# CAP_TCH_4xBUT_CY8CMBR2044.net
KiCad netlist of a schematic drawn in Altium Designer
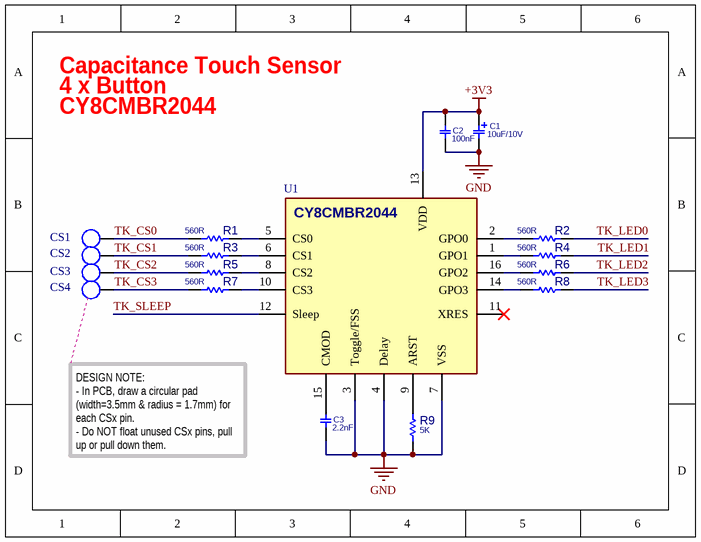
[diagram p0: CAP TCH 4xBUT CY8CMBR2044.SchDoc]

(export (version "E")
  (design (tool "Eeschema 10.0.6"))
  (components
    (comp (ref "C1")
      (value "10uF/10V")
      (footprint "C_TN_3216")
      (description "CAP, SMD, TAN")
      (libsource (lib "Passive") (part "CAP_SMD_TAN"))
    )
    (comp (ref "C2")
      (value "100nF")
      (footprint "C0603")
      (description "CAP, SMD, MLCC")
      (fields (field (name "MANF_P#") "MANF_PART#") (field (name "MANF") "Murata"))
      (libsource (lib "Passive") (part "CAP_SMD_MLCC"))
    )
    (comp (ref "C3")
      (value "2.2nF")
      (footprint "C0603")
      (description "CAP, SMD, MLCC")
      (fields (field (name "MANF_P#") "MANF_PART#") (field (name "MANF") "Murata"))
      (libsource (lib "Passive") (part "CAP_SMD_MLCC"))
    )
    (comp (ref "CS1")
      (value "CAP Sense")
      (footprint "CAP Sense 7mm")
      (libsource (lib "Button") (part "CAP Sense"))
    )
    (comp (ref "CS2")
      (value "CAP Sense")
      (footprint "CAP Sense 7mm")
      (libsource (lib "Button") (part "CAP Sense"))
    )
    (comp (ref "CS3")
      (value "CAP Sense")
      (footprint "CAP Sense 7mm")
      (libsource (lib "Button") (part "CAP Sense"))
    )
    (comp (ref "CS4")
      (value "CAP Sense")
      (footprint "CAP Sense 7mm")
      (libsource (lib "Button") (part "CAP Sense"))
    )
    (comp (ref "R1")
      (value "560R")
      (footprint "R0603")
      (description "RES, SMD")
      (fields (field (name "MANF_P#") "RK73H1ETTP4701F") (field (name "MANF") "KOA SPEER"))
      (libsource (lib "Passive") (part "RES_SMD"))
    )
    (comp (ref "R2")
      (value "560R")
      (footprint "R0603")
      (description "RES, SMD")
      (fields (field (name "MANF_P#") "RK73H1ETTP4701F") (field (name "MANF") "KOA SPEER"))
      (libsource (lib "Passive") (part "RES_SMD"))
    )
    (comp (ref "R3")
      (value "560R")
      (footprint "R0603")
      (description "RES, SMD")
      (fields (field (name "MANF_P#") "RK73H1ETTP4701F") (field (name "MANF") "KOA SPEER"))
      (libsource (lib "Passive") (part "RES_SMD"))
    )
    (comp (ref "R4")
      (value "560R")
      (footprint "R0603")
      (description "RES, SMD")
      (fields (field (name "MANF_P#") "RK73H1ETTP4701F") (field (name "MANF") "KOA SPEER"))
      (libsource (lib "Passive") (part "RES_SMD"))
    )
    (comp (ref "R5")
      (value "560R")
      (footprint "R0603")
      (description "RES, SMD")
      (fields (field (name "MANF_P#") "RK73H1ETTP4701F") (field (name "MANF") "KOA SPEER"))
      (libsource (lib "Passive") (part "RES_SMD"))
    )
    (comp (ref "R6")
      (value "560R")
      (footprint "R0603")
      (description "RES, SMD")
      (fields (field (name "MANF_P#") "RK73H1ETTP4701F") (field (name "MANF") "KOA SPEER"))
      (libsource (lib "Passive") (part "RES_SMD"))
    )
    (comp (ref "R7")
      (value "560R")
      (footprint "R0603")
      (description "RES, SMD")
      (fields (field (name "MANF_P#") "RK73H1ETTP4701F") (field (name "MANF") "KOA SPEER"))
      (libsource (lib "Passive") (part "RES_SMD"))
    )
    (comp (ref "R8")
      (value "560R")
      (footprint "R0603")
      (description "RES, SMD")
      (fields (field (name "MANF_P#") "RK73H1ETTP4701F") (field (name "MANF") "KOA SPEER"))
      (libsource (lib "Passive") (part "RES_SMD"))
    )
    (comp (ref "R9")
      (value "5K")
      (footprint "R0603")
      (description "RES, SMD")
      (fields (field (name "MANF_P#") "RK73H1ETTP4701F") (field (name "MANF") "KOA SPEER"))
      (libsource (lib "Passive") (part "RES_SMD"))
    )
    (comp (ref "U1")
      (value "CY8CMBR2044")
      (footprint "QFN50_16T_3X3")
      (description "CapTouchSensor, 4-CH, QFN16")
      (fields (field (name "MANF") "Microchip") (field (name "MANF_P#") "CAP1208-1-A4"))
      (libsource (lib "Capacitance Touch Sensor") (part "CY8CMBR2044_QFN16"))
    )
  )
  (nets
    (net (code "1") (name "+3V3") (class "Default")
      (node (ref "C1") (pin "1") (pinfunction "1_1") (pintype "passive"))
      (node (ref "C2") (pin "2") (pinfunction "2_2") (pintype "passive"))
      (node (ref "U1") (pin "13") (pinfunction "VDD_13") (pintype "passive"))
    )
    (net (code "2") (name "/TK_CS0") (class "Default")
      (node (ref "CS1") (pin "1") (pinfunction "1_1") (pintype "passive"))
      (node (ref "R1") (pin "1") (pinfunction "1_1") (pintype "passive"))
    )
    (net (code "3") (name "/TK_CS1") (class "Default")
      (node (ref "CS2") (pin "1") (pinfunction "1_1") (pintype "passive"))
      (node (ref "R3") (pin "1") (pinfunction "1_1") (pintype "passive"))
    )
    (net (code "4") (name "/TK_CS2") (class "Default")
      (node (ref "CS3") (pin "1") (pinfunction "1_1") (pintype "passive"))
      (node (ref "R5") (pin "1") (pinfunction "1_1") (pintype "passive"))
    )
    (net (code "5") (name "/TK_CS3") (class "Default")
      (node (ref "CS4") (pin "1") (pinfunction "1_1") (pintype "passive"))
      (node (ref "R7") (pin "1") (pinfunction "1_1") (pintype "passive"))
    )
    (net (code "6") (name "/TK_LED0") (class "Default")
      (node (ref "R2") (pin "2") (pinfunction "2_2") (pintype "passive"))
    )
    (net (code "7") (name "/TK_LED1") (class "Default")
      (node (ref "R4") (pin "2") (pinfunction "2_2") (pintype "passive"))
    )
    (net (code "8") (name "/TK_LED2") (class "Default")
      (node (ref "R6") (pin "2") (pinfunction "2_2") (pintype "passive"))
    )
    (net (code "9") (name "/TK_LED3") (class "Default")
      (node (ref "R8") (pin "2") (pinfunction "2_2") (pintype "passive"))
    )
    (net (code "10") (name "/TK_SLEEP") (class "Default")
      (node (ref "U1") (pin "12") (pinfunction "Sleep_12") (pintype "passive"))
    )
    (net (code "11") (name "GND") (class "Default")
      (node (ref "C1") (pin "2") (pinfunction "2_2") (pintype "passive"))
      (node (ref "C2") (pin "1") (pinfunction "1_1") (pintype "passive"))
      (node (ref "C3") (pin "1") (pinfunction "1_1") (pintype "passive"))
      (node (ref "R9") (pin "1") (pinfunction "1_1") (pintype "passive"))
      (node (ref "U1") (pin "3") (pinfunction "Toggle/FSS_3") (pintype "passive"))
      (node (ref "U1") (pin "4") (pinfunction "Delay_4") (pintype "passive"))
      (node (ref "U1") (pin "7") (pinfunction "VSS_7") (pintype "passive"))
    )
    (net (code "12") (name "Net-(U1-ARST)") (class "Default")
      (node (ref "R9") (pin "2") (pinfunction "2_2") (pintype "passive"))
      (node (ref "U1") (pin "9") (pinfunction "ARST_9") (pintype "passive"))
    )
    (net (code "13") (name "Net-(U1-CMOD)") (class "Default")
      (node (ref "C3") (pin "2") (pinfunction "2_2") (pintype "passive"))
      (node (ref "U1") (pin "15") (pinfunction "CMOD_15") (pintype "passive"))
    )
    (net (code "14") (name "Net-(U1-CS0)") (class "Default")
      (node (ref "R1") (pin "2") (pinfunction "2_2") (pintype "passive"))
      (node (ref "U1") (pin "5") (pinfunction "CS0_5") (pintype "passive"))
    )
    (net (code "15") (name "Net-(U1-CS1)") (class "Default")
      (node (ref "R3") (pin "2") (pinfunction "2_2") (pintype "passive"))
      (node (ref "U1") (pin "6") (pinfunction "CS1_6") (pintype "passive"))
    )
    (net (code "16") (name "Net-(U1-CS2)") (class "Default")
      (node (ref "R5") (pin "2") (pinfunction "2_2") (pintype "passive"))
      (node (ref "U1") (pin "8") (pinfunction "CS2_8") (pintype "passive"))
    )
    (net (code "17") (name "Net-(U1-CS3)") (class "Default")
      (node (ref "R7") (pin "2") (pinfunction "2_2") (pintype "passive"))
      (node (ref "U1") (pin "10") (pinfunction "CS3_10") (pintype "passive"))
    )
    (net (code "18") (name "Net-(U1-GPO0)") (class "Default")
      (node (ref "R2") (pin "1") (pinfunction "1_1") (pintype "passive"))
      (node (ref "U1") (pin "2") (pinfunction "GPO0_2") (pintype "passive"))
    )
    (net (code "19") (name "Net-(U1-GPO1)") (class "Default")
      (node (ref "R4") (pin "1") (pinfunction "1_1") (pintype "passive"))
      (node (ref "U1") (pin "1") (pinfunction "GPO1_1") (pintype "passive"))
    )
    (net (code "20") (name "Net-(U1-GPO2)") (class "Default")
      (node (ref "R6") (pin "1") (pinfunction "1_1") (pintype "passive"))
      (node (ref "U1") (pin "16") (pinfunction "GPO2_16") (pintype "passive"))
    )
    (net (code "21") (name "Net-(U1-GPO3)") (class "Default")
      (node (ref "R8") (pin "1") (pinfunction "1_1") (pintype "passive"))
      (node (ref "U1") (pin "14") (pinfunction "GPO3_14") (pintype "passive"))
    )
    (net (code "22") (name "unconnected-(U1-XRES-Pad11)") (class "Default")
      (node (ref "U1") (pin "11") (pinfunction "XRES_11") (pintype "passive+no_connect"))
    )
  )
)
